# mcu.net
KiCad netlist of a schematic drawn in Altium Designer
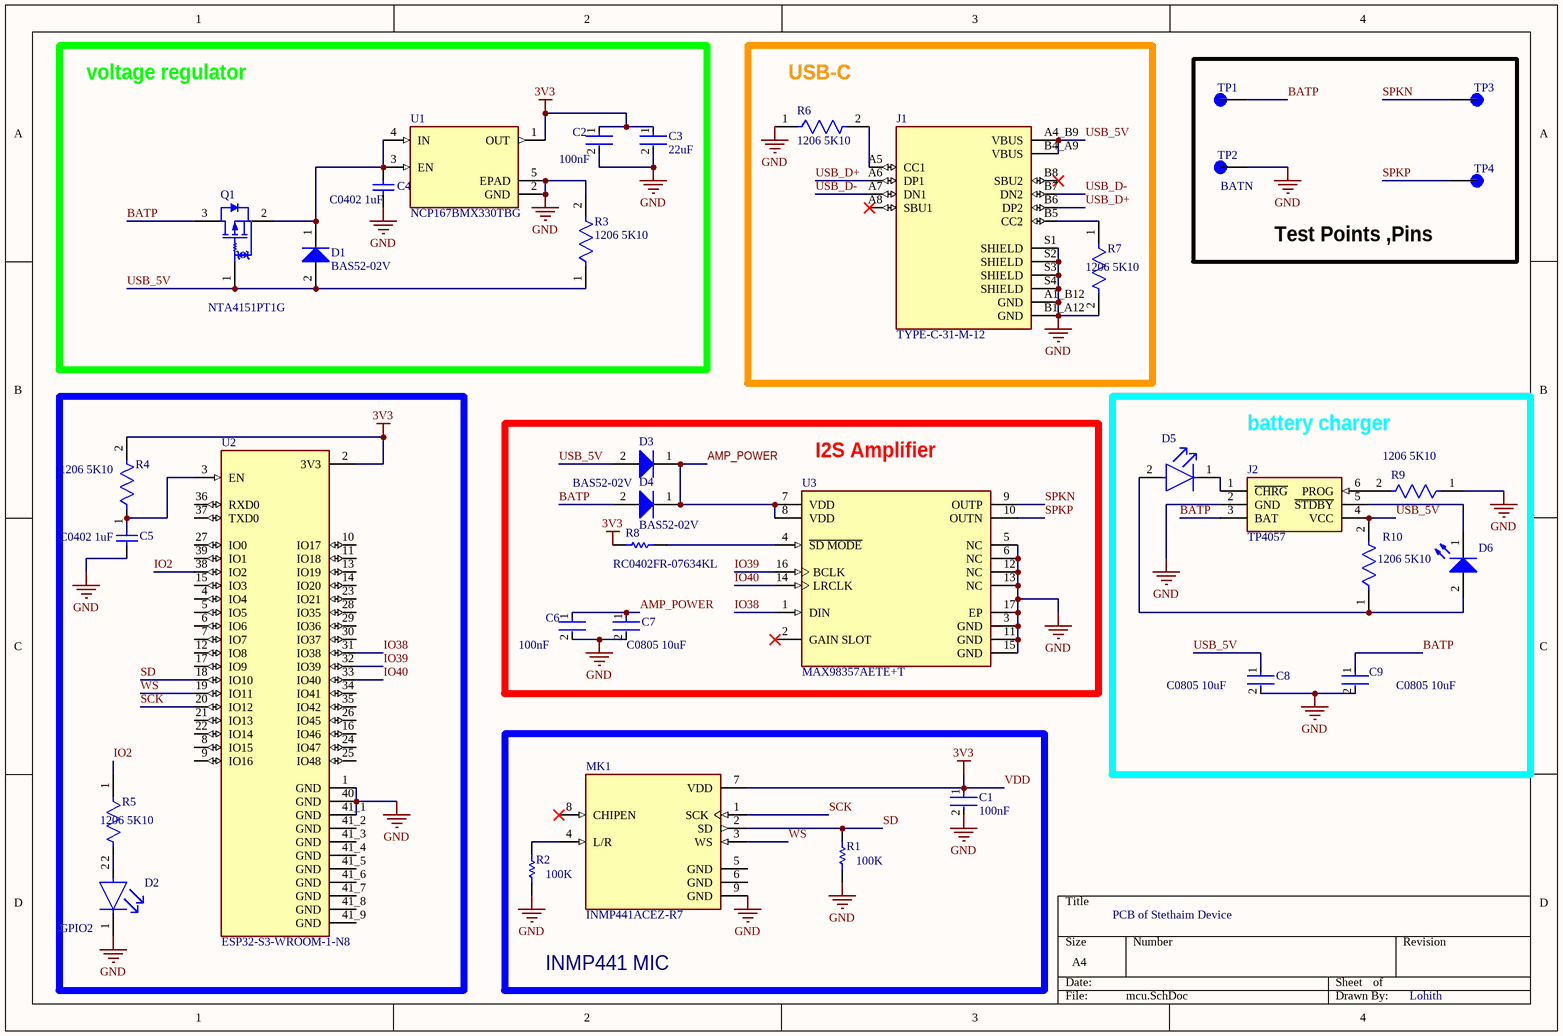
[diagram p0: mcu.SchDoc]

(export (version "E")
  (design (tool "Eeschema 10.0.6"))
  (components
    (comp (ref "C1")
      (value "100nF")
      (footprint "FP-CGA3E-0_3-0_1-IPC_A")
      (description "Cap Ceramic 100nF 50V X7R 10% Pad SMD 0603 +125°C Automotive T/R")
      (fields (field (name "TOLERANCE") "10%") (field (name "VOLTAGE") "50V"))
      (libsource (lib "Altium Content Vault") (part "b4654b650e69147ec39a6b967a45e02"))
    )
    (comp (ref "C2")
      (value "100nF")
      (footprint "FP-CGA3E-0_3-0_1-IPC_A")
      (description "Cap Ceramic 100nF 50V X7R 10% Pad SMD 0603 +125°C Automotive T/R")
      (fields (field (name "TOLERANCE") "10%") (field (name "VOLTAGE") "50V"))
      (libsource (lib "Altium Content Vault") (part "b4654b650e69147ec39a6b967a45e02"))
    )
    (comp (ref "C3")
      (value "22uF")
      (footprint "FP-CC0603-DC-MFG")
      (description "CAP CER 22UF 6.3V X5R 0603")
      (fields (field (name "TOLERANCE") "20%"))
      (libsource (lib "Altium Content Vault") (part "b4654b650e69147ec39a6b967a45e02"))
    )
    (comp (ref "C4")
      (value "C0402 1uF")
      (footprint "CAPC1005X60X30NL05T10")
      (fields (field (name "PART NUMBER") "C0402C105M8PACTU") (field (name "MANUFACTURER") "Kemet"))
      (libsource (lib "Altium Content Vault") (part "CAP"))
    )
    (comp (ref "C5")
      (value "C0402 1uF")
      (footprint "CAPC1005X60X30NL05T10")
      (fields (field (name "PART NUMBER") "C0402C105M8PACTU") (field (name "MANUFACTURER") "Kemet"))
      (libsource (lib "Altium Content Vault") (part "CAP"))
    )
    (comp (ref "C6")
      (value "100nF")
      (footprint "FP-CGA3E-0_3-0_1-IPC_A")
      (description "Cap Ceramic 100nF 50V X7R 10% Pad SMD 0603 +125°C Automotive T/R")
      (fields (field (name "TOLERANCE") "10%") (field (name "VOLTAGE") "50V"))
      (libsource (lib "Altium Content Vault") (part "b4654b650e69147ec39a6b967a45e02"))
    )
    (comp (ref "C7")
      (value "C0805 10uF")
      (footprint "FP-C0805C-DG-MFG")
      (description "CAP CER 10UF 10V X5R 0805")
      (fields (field (name "TOLERANCE") "10%") (field (name "MANUFACTURER PART NUMBER") "C0805C106K8PACTU"))
      (libsource (lib "Altium Content Vault") (part "11868f565c42a9108669ba33697ecf6"))
    )
    (comp (ref "C8")
      (value "C0805 10uF")
      (footprint "FP-C0805C-DG-MFG")
      (description "CAP CER 10UF 10V X5R 0805")
      (fields (field (name "TOLERANCE") "10%") (field (name "MANUFACTURER PART NUMBER") "C0805C106K8PACTU"))
      (libsource (lib "Altium Content Vault") (part "11868f565c42a9108669ba33697ecf6"))
    )
    (comp (ref "C9")
      (value "C0805 10uF")
      (footprint "FP-C0805C-DG-MFG")
      (description "CAP CER 10UF 10V X5R 0805")
      (fields (field (name "TOLERANCE") "10%") (field (name "MANUFACTURER PART NUMBER") "C0805C106K8PACTU"))
      (libsource (lib "Altium Content Vault") (part "11868f565c42a9108669ba33697ecf6"))
    )
    (comp (ref "D1")
      (value "BAS52-02V")
      (footprint "INF-SC79_V")
      (description "Silicon Schottky Diode, SC79, Reel, Green")
      (fields (field (name "MANUFACTURER") "Infineon"))
      (libsource (lib "Altium Content Vault") (part "INF-D_K1A2-2"))
    )
    (comp (ref "D2")
      (value "GPIO2")
      (footprint "FP-LTST-C190KRKT-MFG")
      (description "LED RED CLEAR CHIP SMD")
      (libsource (lib "Altium Content Vault") (part "8706943c75ba83719d021d2fdc84c58"))
    )
    (comp (ref "D3")
      (value "BAS52-02V")
      (footprint "INF-SC79_V")
      (description "Silicon Schottky Diode, SC79, Reel, Green")
      (fields (field (name "MANUFACTURER") "Infineon"))
      (libsource (lib "Altium Content Vault") (part "INF-D_K1A2-2"))
    )
    (comp (ref "D4")
      (value "BAS52-02V")
      (footprint "INF-SC79_V")
      (description "Silicon Schottky Diode, SC79, Reel, Green")
      (fields (field (name "MANUFACTURER") "Infineon"))
      (libsource (lib "Altium Content Vault") (part "INF-D_K1A2-2"))
    )
    (comp (ref "D5")
      (value "PTD3216CGCK")
      (footprint "FP-APTD3216CGCK-MFG")
      (description "LED GREEN CLEAR 2SMD")
      (libsource (lib "Altium Content Vault") (part "8706943c75ba83719d021d2fdc84c58"))
    )
    (comp (ref "D6")
      (value "150120BS75000")
      (footprint "WL-SMCW_1206_150120xx75000")
      (libsource (lib "Altium Content Vault") (part "LED_Blue_2A-1K"))
    )
    (comp (ref "J1")
      (value "TYPE-C-31-M-12")
      (footprint "HRO_TYPE-C-31-M-12")
      (description "USB Connectors 24 Receptacle 1 8.94*7.3mm RoHS")
      (fields (field (name "MF") "HRO Electronics Co., Ltd."))
      (libsource (lib "workspace1") (part "TYPE-C-31-M-12"))
    )
    (comp (ref "J2")
      (value "TP4057")
      (footprint "SOT23-6")
      (fields (field (name "MF") "toppower"))
      (libsource (lib "TP4057") (part "TP4057"))
    )
    (comp (ref "MK1")
      (value "INMP441ACEZ-R7")
      (footprint "MIC_INMP441ACEZ-R7")
      (fields (field (name "MF") "TDK InvenSense"))
      (libsource (lib "workspace1") (part "INMP441ACEZ-R7"))
    )
    (comp (ref "Q1")
      (value "NTA4151PT1G")
      (footprint "ONSC-SC-75-3-463-01_V")
      (fields (field (name "MANUFACTURER") "On Semiconductor"))
      (libsource (lib "Altium Content Vault") (part "ONSC-PMOS-G1S2D3-3_C"))
    )
    (comp (ref "R1")
      (value "100K")
      (footprint "RESC3116X65X40ML10T20")
      (description "Chip Resistor, 100 KOhm, +/- 1%, 0.25 W, -55 to 155 degC, 1206 (3216 Metric), RoHS, Tape and Reel")
      (fields (field (name "TOLERANCE") "1%") (field (name "MANUFACTURER") "Yageo"))
      (libsource (lib "Altium Content Vault") (part "RES-2"))
    )
    (comp (ref "R2")
      (value "100K")
      (footprint "RESC3116X65X40ML10T20")
      (description "Chip Resistor, 100 KOhm, +/- 1%, 0.25 W, -55 to 155 degC, 1206 (3216 Metric), RoHS, Tape and Reel")
      (fields (field (name "TOLERANCE") "1%") (field (name "MANUFACTURER") "Yageo"))
      (libsource (lib "Altium Content Vault") (part "RES-2"))
    )
    (comp (ref "R3")
      (value "1206 5K10")
      (footprint "FP-RMCF1206-IPC_C")
      (description "5.1kΩ ±5% 0.25W 1206 Thick Film Chip Resistor AEC-Q200 compliant")
      (fields (field (name "TOLERANCE") "5%"))
      (libsource (lib "Altium Content Vault") (part "1029c3af85768c4190bb7ad29bc67b5"))
    )
    (comp (ref "R4")
      (value "1206 5K10")
      (footprint "FP-RMCF1206-IPC_C")
      (description "5.1kΩ ±5% 0.25W 1206 Thick Film Chip Resistor AEC-Q200 compliant")
      (fields (field (name "TOLERANCE") "5%"))
      (libsource (lib "Altium Content Vault") (part "1029c3af85768c4190bb7ad29bc67b5"))
    )
    (comp (ref "R5")
      (value "1206 5K10")
      (footprint "FP-RMCF1206-IPC_C")
      (description "5.1kΩ ±5% 0.25W 1206 Thick Film Chip Resistor AEC-Q200 compliant")
      (fields (field (name "TOLERANCE") "5%"))
      (libsource (lib "Altium Content Vault") (part "1029c3af85768c4190bb7ad29bc67b5"))
    )
    (comp (ref "R6")
      (value "1206 5K10")
      (footprint "FP-RMCF1206-IPC_C")
      (description "5.1kΩ ±5% 0.25W 1206 Thick Film Chip Resistor AEC-Q200 compliant")
      (fields (field (name "TOLERANCE") "5%"))
      (libsource (lib "Altium Content Vault") (part "1029c3af85768c4190bb7ad29bc67b5"))
    )
    (comp (ref "R7")
      (value "1206 5K10")
      (footprint "FP-RMCF1206-IPC_C")
      (description "5.1kΩ ±5% 0.25W 1206 Thick Film Chip Resistor AEC-Q200 compliant")
      (fields (field (name "TOLERANCE") "5%"))
      (libsource (lib "Altium Content Vault") (part "1029c3af85768c4190bb7ad29bc67b5"))
    )
    (comp (ref "R8")
      (value "RC0402FR-07634KL")
      (footprint "RESC1005X40X25LL05T10")
      (fields (field (name "MANUFACTURER") "Yageo / Phycomp"))
      (libsource (lib "Altium Content Vault") (part "RES"))
    )
    (comp (ref "R9")
      (value "1206 5K10")
      (footprint "FP-RMCF1206-IPC_C")
      (description "5.1kΩ ±5% 0.25W 1206 Thick Film Chip Resistor AEC-Q200 compliant")
      (fields (field (name "TOLERANCE") "5%"))
      (libsource (lib "Altium Content Vault") (part "1029c3af85768c4190bb7ad29bc67b5"))
    )
    (comp (ref "R10")
      (value "1206 5K10")
      (footprint "FP-RMCF1206-IPC_C")
      (description "5.1kΩ ±5% 0.25W 1206 Thick Film Chip Resistor AEC-Q200 compliant")
      (fields (field (name "TOLERANCE") "5%"))
      (libsource (lib "Altium Content Vault") (part "1029c3af85768c4190bb7ad29bc67b5"))
    )
    (comp (ref "TP1")
      (value "5019")
      (footprint "KEYSTONE_5019")
      (description "SMT Test Point- Mininature-1000 pc Reels")
      (fields (field (name "MF") "Keystone Electronics"))
      (libsource (lib "5019") (part "5019"))
    )
    (comp (ref "TP2")
      (value "BATN")
      (footprint "KEYSTONE_5019")
      (description "SMT Test Point- Mininature-1000 pc Reels")
      (fields (field (name "MP") "5019") (field (name "MF") "Keystone Electronics"))
      (libsource (lib "5019") (part "5019"))
    )
    (comp (ref "TP3")
      (value "5019")
      (footprint "KEYSTONE_5019")
      (description "SMT Test Point- Mininature-1000 pc Reels")
      (fields (field (name "MF") "Keystone Electronics"))
      (libsource (lib "5019") (part "5019"))
    )
    (comp (ref "TP4")
      (value "5019")
      (footprint "KEYSTONE_5019")
      (description "SMT Test Point- Mininature-1000 pc Reels")
      (fields (field (name "MF") "Keystone Electronics"))
      (libsource (lib "5019") (part "5019"))
    )
    (comp (ref "U1")
      (value "NCP167BMX330TBG")
      (footprint "VREG_NCP167BMX330TBG")
      (description "Linear Voltage Regulator IC Positive Fixed 1 Output 700mA 4-XDFN (1x1)")
      (fields (field (name "MF") "onsemi"))
      (libsource (lib "NCP167BMX330TBG") (part "NCP167BMX330TBG"))
    )
    (comp (ref "U2")
      (value "ESP32-S3-WROOM-1-N8")
      (footprint "XCVR_ESP32-S3-WROOM-1-N8")
      (fields (field (name "MF") "{'manufacturer': u'Espressif Systems'}"))
      (libsource (lib "workspace1") (part "ESP32-S3-WROOM-1-N8"))
    )
    (comp (ref "U3")
      (value "MAX98357AETE+T")
      (footprint "FP-T1633-4-MFG")
      (description "IC AMP CLASS D MONO 3.2W 16TQFN")
      (libsource (lib "Altium Content Vault") (part "902df0143a84dfa2dd990dcc5368a09"))
    )
  )
  (nets
    (net (code "1") (name "/AMP_POWER") (class "Default")
      (node (ref "C6") (pin "1") (pinfunction "1_1") (pintype "passive"))
      (node (ref "C7") (pin "1") (pinfunction "1_1") (pintype "passive"))
      (node (ref "D3") (pin "1") (pinfunction "K_1") (pintype "passive"))
      (node (ref "D4") (pin "1") (pinfunction "K_1") (pintype "passive"))
      (node (ref "U3") (pin "7") (pinfunction "VDD_7") (pintype "power_in"))
      (node (ref "U3") (pin "8") (pinfunction "VDD_8") (pintype "power_in"))
    )
    (net (code "2") (name "/BATP") (class "Default")
      (node (ref "C9") (pin "1") (pinfunction "1_1") (pintype "passive"))
      (node (ref "D4") (pin "2") (pinfunction "A_2") (pintype "passive"))
      (node (ref "J2") (pin "3") (pinfunction "BAT_3") (pintype "power_in"))
      (node (ref "Q1") (pin "3") (pinfunction "D_3") (pintype "passive"))
      (node (ref "TP1") (pin "TP") (pinfunction "TP_TP") (pintype "passive"))
    )
    (net (code "3") (name "/IO2") (class "Default")
      (node (ref "R5") (pin "1") (pinfunction "1_1") (pintype "passive"))
      (node (ref "U2") (pin "38") (pinfunction "IO2_38") (pintype "bidirectional"))
    )
    (net (code "4") (name "/IO38") (class "Default")
      (node (ref "U2") (pin "31") (pinfunction "IO38_31") (pintype "bidirectional"))
      (node (ref "U3") (pin "1") (pinfunction "DIN_1") (pintype "input"))
    )
    (net (code "5") (name "/IO39") (class "Default")
      (node (ref "U2") (pin "32") (pinfunction "IO39_32") (pintype "bidirectional"))
      (node (ref "U3") (pin "16") (pinfunction "BCLK_16") (pintype "input"))
    )
    (net (code "6") (name "/IO40") (class "Default")
      (node (ref "U2") (pin "33") (pinfunction "IO40_33") (pintype "bidirectional"))
      (node (ref "U3") (pin "14") (pinfunction "LRCLK_14") (pintype "input"))
    )
    (net (code "7") (name "/SCK") (class "Default")
      (node (ref "MK1") (pin "1") (pinfunction "SCK_1") (pintype "input"))
      (node (ref "U2") (pin "20") (pinfunction "IO12_20") (pintype "bidirectional"))
    )
    (net (code "8") (name "/SD") (class "Default")
      (node (ref "MK1") (pin "2") (pinfunction "SD_2") (pintype "output"))
      (node (ref "R1") (pin "2") (pinfunction "2_2") (pintype "passive"))
      (node (ref "U2") (pin "18") (pinfunction "IO10_18") (pintype "bidirectional"))
    )
    (net (code "9") (name "/SPKN") (class "Default")
      (node (ref "TP3") (pin "TP") (pinfunction "TP_TP") (pintype "passive"))
      (node (ref "U3") (pin "9") (pinfunction "OUTP_9") (pintype "passive"))
    )
    (net (code "10") (name "/SPKP") (class "Default")
      (node (ref "TP4") (pin "TP") (pinfunction "TP_TP") (pintype "passive"))
      (node (ref "U3") (pin "10") (pinfunction "OUTN_10") (pintype "passive"))
    )
    (net (code "11") (name "/USB_5V") (class "Default")
      (node (ref "C8") (pin "1") (pinfunction "1_1") (pintype "passive"))
      (node (ref "D1") (pin "2") (pinfunction "A_2") (pintype "passive"))
      (node (ref "D3") (pin "2") (pinfunction "A_2") (pintype "passive"))
      (node (ref "J1") (pin "A4_B9") (pinfunction "VBUS_A4_B9") (pintype "power_in"))
      (node (ref "J1") (pin "B4_A9") (pinfunction "VBUS_B4_A9") (pintype "power_in"))
      (node (ref "J2") (pin "4") (pinfunction "VCC_4") (pintype "power_in"))
      (node (ref "Q1") (pin "1") (pinfunction "G_1") (pintype "passive"))
      (node (ref "R10") (pin "2") (pinfunction "2_2") (pintype "passive"))
      (node (ref "R3") (pin "1") (pinfunction "1_1") (pintype "passive"))
    )
    (net (code "12") (name "/USB_D+") (class "Default")
      (node (ref "J1") (pin "A6") (pinfunction "DP1_A6") (pintype "bidirectional"))
      (node (ref "J1") (pin "B6") (pinfunction "DP2_B6") (pintype "bidirectional"))
    )
    (net (code "13") (name "/USB_D-") (class "Default")
      (node (ref "J1") (pin "A7") (pinfunction "DN1_A7") (pintype "bidirectional"))
      (node (ref "J1") (pin "B7") (pinfunction "DN2_B7") (pintype "bidirectional"))
    )
    (net (code "14") (name "/WS") (class "Default")
      (node (ref "MK1") (pin "3") (pinfunction "WS_3") (pintype "input"))
      (node (ref "U2") (pin "19") (pinfunction "IO11_19") (pintype "bidirectional"))
    )
    (net (code "15") (name "3V3") (class "Default")
      (node (ref "C1") (pin "1") (pinfunction "1_1") (pintype "passive"))
      (node (ref "C2") (pin "1") (pinfunction "1_1") (pintype "passive"))
      (node (ref "C3") (pin "1") (pinfunction "1_1") (pintype "passive"))
      (node (ref "MK1") (pin "7") (pinfunction "VDD_7") (pintype "power_in"))
      (node (ref "R4") (pin "2") (pinfunction "2_2") (pintype "passive"))
      (node (ref "R8") (pin "1") (pinfunction "1_1") (pintype "passive"))
      (node (ref "U1") (pin "1") (pinfunction "OUT_1") (pintype "output"))
      (node (ref "U2") (pin "2") (pinfunction "3V3_2") (pintype "power_in"))
    )
    (net (code "16") (name "GND") (class "Default")
      (node (ref "C1") (pin "2") (pinfunction "2_2") (pintype "passive"))
      (node (ref "C2") (pin "2") (pinfunction "2_2") (pintype "passive"))
      (node (ref "C3") (pin "2") (pinfunction "2_2") (pintype "passive"))
      (node (ref "C4") (pin "1") (pinfunction "1_1") (pintype "passive"))
      (node (ref "C5") (pin "1") (pinfunction "1_1") (pintype "passive"))
      (node (ref "C6") (pin "2") (pinfunction "2_2") (pintype "passive"))
      (node (ref "C7") (pin "2") (pinfunction "2_2") (pintype "passive"))
      (node (ref "C8") (pin "2") (pinfunction "2_2") (pintype "passive"))
      (node (ref "C9") (pin "2") (pinfunction "2_2") (pintype "passive"))
      (node (ref "D2") (pin "1") (pinfunction "C_1") (pintype "passive"))
      (node (ref "J1") (pin "A1_B12") (pinfunction "GND_A1_B12") (pintype "power_in"))
      (node (ref "J1") (pin "B1_A12") (pinfunction "GND_B1_A12") (pintype "power_in"))
      (node (ref "J1") (pin "S1") (pinfunction "SHIELD_S1") (pintype "passive"))
      (node (ref "J1") (pin "S2") (pinfunction "SHIELD_S2") (pintype "passive"))
      (node (ref "J1") (pin "S3") (pinfunction "SHIELD_S3") (pintype "passive"))
      (node (ref "J1") (pin "S4") (pinfunction "SHIELD_S4") (pintype "passive"))
      (node (ref "J2") (pin "2") (pinfunction "GND_2") (pintype "power_in"))
      (node (ref "MK1") (pin "9") (pinfunction "GND_9") (pintype "power_in"))
      (node (ref "R1") (pin "1") (pinfunction "1_1") (pintype "passive"))
      (node (ref "R2") (pin "1") (pinfunction "1_1") (pintype "passive"))
      (node (ref "R3") (pin "2") (pinfunction "2_2") (pintype "passive"))
      (node (ref "R6") (pin "1") (pinfunction "1_1") (pintype "passive"))
      (node (ref "R7") (pin "2") (pinfunction "2_2") (pintype "passive"))
      (node (ref "R9") (pin "1") (pinfunction "1_1") (pintype "passive"))
      (node (ref "TP2") (pin "TP") (pinfunction "TP_TP") (pintype "passive"))
      (node (ref "U1") (pin "2") (pinfunction "GND_2") (pintype "power_in"))
      (node (ref "U1") (pin "5") (pinfunction "EPAD_5") (pintype "power_in"))
      (node (ref "U2") (pin "1") (pinfunction "GND_1") (pintype "power_in"))
      (node (ref "U2") (pin "40") (pinfunction "GND_40") (pintype "power_in"))
      (node (ref "U2") (pin "41_1") (pinfunction "GND_41_1") (pintype "power_in"))
      (node (ref "U3") (pin "11") (pinfunction "GND_11") (pintype "power_in"))
      (node (ref "U3") (pin "12") (pinfunction "NC_12") (pintype "passive"))
      (node (ref "U3") (pin "13") (pinfunction "NC_13") (pintype "passive"))
      (node (ref "U3") (pin "15") (pinfunction "GND_15") (pintype "power_in"))
      (node (ref "U3") (pin "17") (pinfunction "EP_17") (pintype "passive"))
      (node (ref "U3") (pin "3") (pinfunction "GND_3") (pintype "power_in"))
      (node (ref "U3") (pin "5") (pinfunction "NC_5") (pintype "passive"))
      (node (ref "U3") (pin "6") (pinfunction "NC_6") (pintype "passive"))
    )
    (net (code "17") (name "Net-(D1-K)") (class "Default")
      (node (ref "C4") (pin "2") (pinfunction "2_2") (pintype "passive"))
      (node (ref "D1") (pin "1") (pinfunction "K_1") (pintype "passive"))
      (node (ref "Q1") (pin "2") (pinfunction "S_2") (pintype "passive"))
      (node (ref "U1") (pin "3") (pinfunction "EN_3") (pintype "input"))
      (node (ref "U1") (pin "4") (pinfunction "IN_4") (pintype "input"))
    )
    (net (code "18") (name "Net-(D2-A)") (class "Default")
      (node (ref "D2") (pin "2") (pinfunction "A_2") (pintype "passive"))
      (node (ref "R5") (pin "2") (pinfunction "2_2") (pintype "passive"))
    )
    (net (code "19") (name "Net-(D5-A)") (class "Default")
      (node (ref "D5") (pin "2") (pinfunction "A_2") (pintype "passive"))
      (node (ref "D6") (pin "2") (pinfunction "A_2") (pintype "passive"))
      (node (ref "R10") (pin "1") (pinfunction "1_1") (pintype "passive"))
    )
    (net (code "20") (name "Net-(D5-C)") (class "Default")
      (node (ref "D5") (pin "1") (pinfunction "C_1") (pintype "passive"))
      (node (ref "J2") (pin "1") (pinfunction "~{CHRG}_1") (pintype "open_collector"))
    )
    (net (code "21") (name "Net-(D6-K)") (class "Default")
      (node (ref "D6") (pin "1") (pinfunction "K_1") (pintype "passive"))
      (node (ref "J2") (pin "5") (pinfunction "~{STDBY}_5") (pintype "open_collector"))
    )
    (net (code "22") (name "Net-(J1-CC1)") (class "Default")
      (node (ref "J1") (pin "A5") (pinfunction "CC1_A5") (pintype "bidirectional"))
      (node (ref "R6") (pin "2") (pinfunction "2_2") (pintype "passive"))
    )
    (net (code "23") (name "Net-(J1-CC2)") (class "Default")
      (node (ref "J1") (pin "B5") (pinfunction "CC2_B5") (pintype "bidirectional"))
      (node (ref "R7") (pin "1") (pinfunction "1_1") (pintype "passive"))
    )
    (net (code "24") (name "Net-(J2-PROG)") (class "Default")
      (node (ref "J2") (pin "6") (pinfunction "PROG_6") (pintype "input"))
      (node (ref "R9") (pin "2") (pinfunction "2_2") (pintype "passive"))
    )
    (net (code "25") (name "Net-(MK1-L{slash}R)") (class "Default")
      (node (ref "MK1") (pin "4") (pinfunction "L/R_4") (pintype "input"))
      (node (ref "R2") (pin "2") (pinfunction "2_2") (pintype "passive"))
    )
    (net (code "26") (name "Net-(U2-EN)") (class "Default")
      (node (ref "C5") (pin "2") (pinfunction "2_2") (pintype "passive"))
      (node (ref "R4") (pin "1") (pinfunction "1_1") (pintype "passive"))
      (node (ref "U2") (pin "3") (pinfunction "EN_3") (pintype "input"))
    )
    (net (code "27") (name "Net-(U3-~{SD_MODE})") (class "Default")
      (node (ref "R8") (pin "2") (pinfunction "2_2") (pintype "passive"))
      (node (ref "U3") (pin "4") (pinfunction "~{SD_MODE}_4") (pintype "input"))
    )
    (net (code "28") (name "unconnected-(J1-SBU1-PadA8)") (class "Default")
      (node (ref "J1") (pin "A8") (pinfunction "SBU1_A8") (pintype "bidirectional+no_connect"))
    )
    (net (code "29") (name "unconnected-(J1-SBU2-PadB8)") (class "Default")
      (node (ref "J1") (pin "B8") (pinfunction "SBU2_B8") (pintype "bidirectional+no_connect"))
    )
    (net (code "30") (name "unconnected-(MK1-CHIPEN-Pad8)") (class "Default")
      (node (ref "MK1") (pin "8") (pinfunction "CHIPEN_8") (pintype "input+no_connect"))
    )
    (net (code "31") (name "unconnected-(MK1-GND-Pad5)") (class "Default")
      (node (ref "MK1") (pin "5") (pinfunction "GND_5") (pintype "power_in"))
    )
    (net (code "32") (name "unconnected-(MK1-GND-Pad6)") (class "Default")
      (node (ref "MK1") (pin "6") (pinfunction "GND_6") (pintype "power_in"))
    )
    (net (code "33") (name "unconnected-(U2-GND-Pad41_2)") (class "Default")
      (node (ref "U2") (pin "41_2") (pinfunction "GND_41_2") (pintype "power_in"))
    )
    (net (code "34") (name "unconnected-(U2-GND-Pad41_3)") (class "Default")
      (node (ref "U2") (pin "41_3") (pinfunction "GND_41_3") (pintype "power_in"))
    )
    (net (code "35") (name "unconnected-(U2-GND-Pad41_4)") (class "Default")
      (node (ref "U2") (pin "41_4") (pinfunction "GND_41_4") (pintype "power_in"))
    )
    (net (code "36") (name "unconnected-(U2-GND-Pad41_5)") (class "Default")
      (node (ref "U2") (pin "41_5") (pinfunction "GND_41_5") (pintype "power_in"))
    )
    (net (code "37") (name "unconnected-(U2-GND-Pad41_6)") (class "Default")
      (node (ref "U2") (pin "41_6") (pinfunction "GND_41_6") (pintype "power_in"))
    )
    (net (code "38") (name "unconnected-(U2-GND-Pad41_7)") (class "Default")
      (node (ref "U2") (pin "41_7") (pinfunction "GND_41_7") (pintype "power_in"))
    )
    (net (code "39") (name "unconnected-(U2-GND-Pad41_8)") (class "Default")
      (node (ref "U2") (pin "41_8") (pinfunction "GND_41_8") (pintype "power_in"))
    )
    (net (code "40") (name "unconnected-(U2-GND-Pad41_9)") (class "Default")
      (node (ref "U2") (pin "41_9") (pinfunction "GND_41_9") (pintype "power_in"))
    )
    (net (code "41") (name "unconnected-(U2-IO0-Pad27)") (class "Default")
      (node (ref "U2") (pin "27") (pinfunction "IO0_27") (pintype "bidirectional"))
    )
    (net (code "42") (name "unconnected-(U2-IO1-Pad39)") (class "Default")
      (node (ref "U2") (pin "39") (pinfunction "IO1_39") (pintype "bidirectional"))
    )
    (net (code "43") (name "unconnected-(U2-IO3-Pad15)") (class "Default")
      (node (ref "U2") (pin "15") (pinfunction "IO3_15") (pintype "bidirectional"))
    )
    (net (code "44") (name "unconnected-(U2-IO4-Pad4)") (class "Default")
      (node (ref "U2") (pin "4") (pinfunction "IO4_4") (pintype "bidirectional"))
    )
    (net (code "45") (name "unconnected-(U2-IO5-Pad5)") (class "Default")
      (node (ref "U2") (pin "5") (pinfunction "IO5_5") (pintype "bidirectional"))
    )
    (net (code "46") (name "unconnected-(U2-IO6-Pad6)") (class "Default")
      (node (ref "U2") (pin "6") (pinfunction "IO6_6") (pintype "bidirectional"))
    )
    (net (code "47") (name "unconnected-(U2-IO7-Pad7)") (class "Default")
      (node (ref "U2") (pin "7") (pinfunction "IO7_7") (pintype "bidirectional"))
    )
    (net (code "48") (name "unconnected-(U2-IO8-Pad12)") (class "Default")
      (node (ref "U2") (pin "12") (pinfunction "IO8_12") (pintype "bidirectional"))
    )
    (net (code "49") (name "unconnected-(U2-IO9-Pad17)") (class "Default")
      (node (ref "U2") (pin "17") (pinfunction "IO9_17") (pintype "bidirectional"))
    )
    (net (code "50") (name "unconnected-(U2-IO13-Pad21)") (class "Default")
      (node (ref "U2") (pin "21") (pinfunction "IO13_21") (pintype "bidirectional"))
    )
    (net (code "51") (name "unconnected-(U2-IO14-Pad22)") (class "Default")
      (node (ref "U2") (pin "22") (pinfunction "IO14_22") (pintype "bidirectional"))
    )
    (net (code "52") (name "unconnected-(U2-IO15-Pad8)") (class "Default")
      (node (ref "U2") (pin "8") (pinfunction "IO15_8") (pintype "bidirectional"))
    )
    (net (code "53") (name "unconnected-(U2-IO16-Pad9)") (class "Default")
      (node (ref "U2") (pin "9") (pinfunction "IO16_9") (pintype "bidirectional"))
    )
    (net (code "54") (name "unconnected-(U2-IO17-Pad10)") (class "Default")
      (node (ref "U2") (pin "10") (pinfunction "IO17_10") (pintype "bidirectional"))
    )
    (net (code "55") (name "unconnected-(U2-IO18-Pad11)") (class "Default")
      (node (ref "U2") (pin "11") (pinfunction "IO18_11") (pintype "bidirectional"))
    )
    (net (code "56") (name "unconnected-(U2-IO19-Pad13)") (class "Default")
      (node (ref "U2") (pin "13") (pinfunction "IO19_13") (pintype "bidirectional"))
    )
    (net (code "57") (name "unconnected-(U2-IO20-Pad14)") (class "Default")
      (node (ref "U2") (pin "14") (pinfunction "IO20_14") (pintype "bidirectional"))
    )
    (net (code "58") (name "unconnected-(U2-IO21-Pad23)") (class "Default")
      (node (ref "U2") (pin "23") (pinfunction "IO21_23") (pintype "bidirectional"))
    )
    (net (code "59") (name "unconnected-(U2-IO35-Pad28)") (class "Default")
      (node (ref "U2") (pin "28") (pinfunction "IO35_28") (pintype "bidirectional"))
    )
    (net (code "60") (name "unconnected-(U2-IO36-Pad29)") (class "Default")
      (node (ref "U2") (pin "29") (pinfunction "IO36_29") (pintype "bidirectional"))
    )
    (net (code "61") (name "unconnected-(U2-IO37-Pad30)") (class "Default")
      (node (ref "U2") (pin "30") (pinfunction "IO37_30") (pintype "bidirectional"))
    )
    (net (code "62") (name "unconnected-(U2-IO41-Pad34)") (class "Default")
      (node (ref "U2") (pin "34") (pinfunction "IO41_34") (pintype "bidirectional"))
    )
    (net (code "63") (name "unconnected-(U2-IO42-Pad35)") (class "Default")
      (node (ref "U2") (pin "35") (pinfunction "IO42_35") (pintype "bidirectional"))
    )
    (net (code "64") (name "unconnected-(U2-IO45-Pad26)") (class "Default")
      (node (ref "U2") (pin "26") (pinfunction "IO45_26") (pintype "bidirectional"))
    )
    (net (code "65") (name "unconnected-(U2-IO46-Pad16)") (class "Default")
      (node (ref "U2") (pin "16") (pinfunction "IO46_16") (pintype "bidirectional"))
    )
    (net (code "66") (name "unconnected-(U2-IO47-Pad24)") (class "Default")
      (node (ref "U2") (pin "24") (pinfunction "IO47_24") (pintype "bidirectional"))
    )
    (net (code "67") (name "unconnected-(U2-IO48-Pad25)") (class "Default")
      (node (ref "U2") (pin "25") (pinfunction "IO48_25") (pintype "bidirectional"))
    )
    (net (code "68") (name "unconnected-(U2-RXD0-Pad36)") (class "Default")
      (node (ref "U2") (pin "36") (pinfunction "RXD0_36") (pintype "bidirectional"))
    )
    (net (code "69") (name "unconnected-(U2-TXD0-Pad37)") (class "Default")
      (node (ref "U2") (pin "37") (pinfunction "TXD0_37") (pintype "bidirectional"))
    )
    (net (code "70") (name "unconnected-(U3-GAIN_SLOT-Pad2)") (class "Default")
      (node (ref "U3") (pin "2") (pinfunction "GAIN_SLOT_2") (pintype "passive+no_connect"))
    )
  )
)
